# 80PIN_FMU_REV_1B.net
KiCad netlist of a schematic drawn in Altium Designer
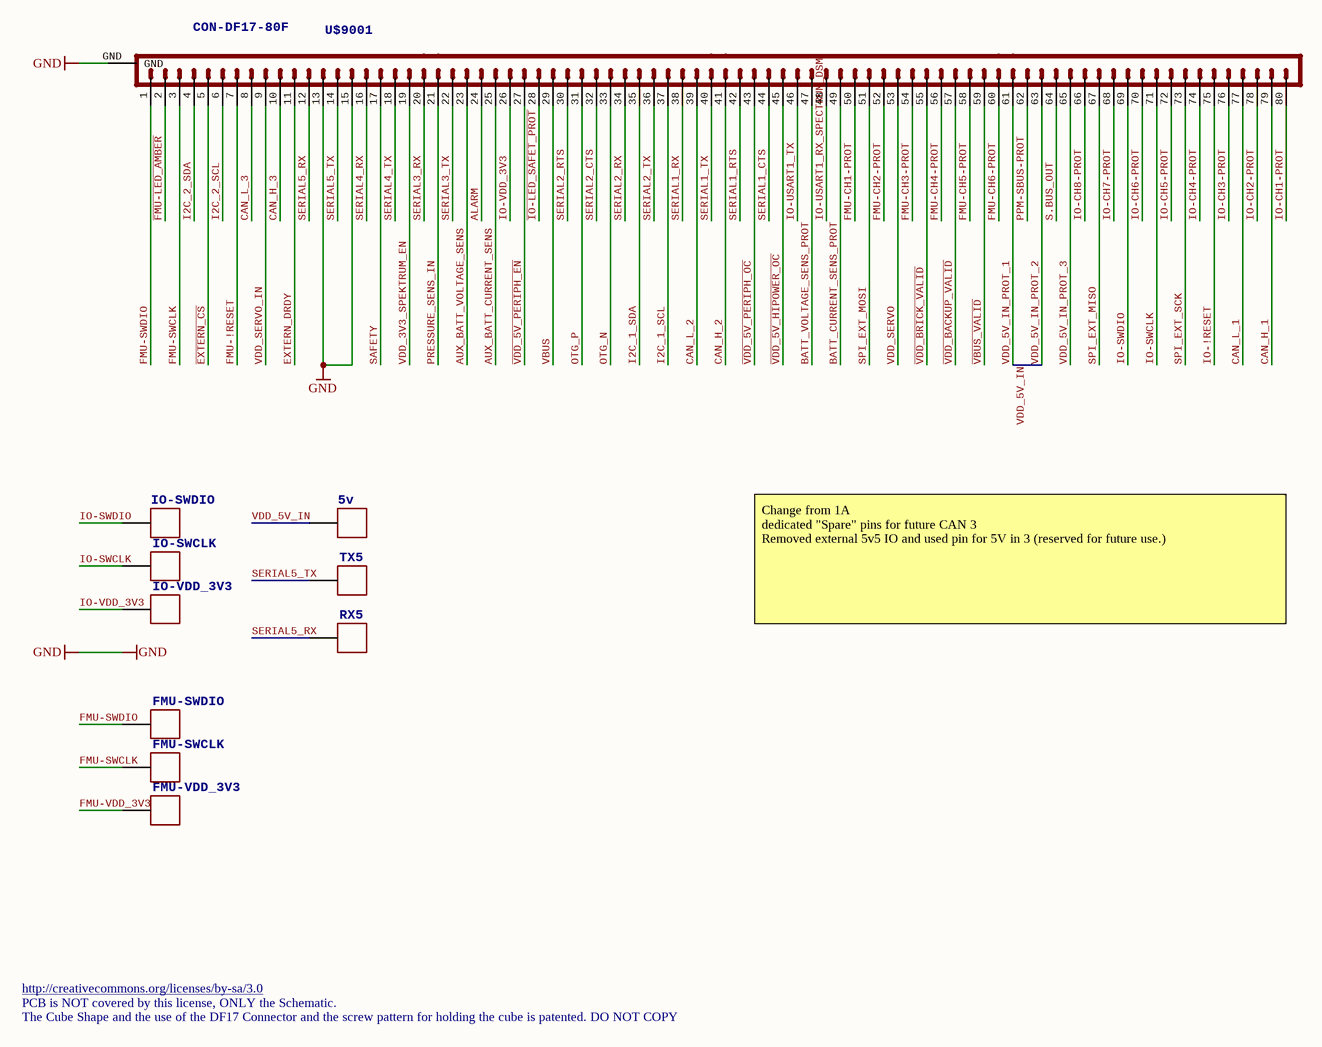
[diagram p0: 80PIN_FMU_REV_1B.SchDoc]

(export (version "E")
  (design (tool "Eeschema 10.0.6"))
  (components
    (comp (ref "5v") (value "PAD.04") (footprint "PAD.04X.04") (libsource (lib "pixhawk2") (part "PAD.04")))
    (comp (ref "FMU-SWCLK")
      (value "PAD.04")
      (footprint "PAD.04X.04")
      (libsource (lib "pixhawk2") (part "PAD.04"))
    )
    (comp (ref "FMU-SWDIO")
      (value "PAD.04")
      (footprint "PAD.04X.04")
      (libsource (lib "pixhawk2") (part "PAD.04"))
    )
    (comp (ref "FMU-VDD_3V3")
      (value "PAD.04")
      (footprint "PAD.04X.04")
      (libsource (lib "pixhawk2") (part "PAD.04"))
    )
    (comp (ref "IO-SWCLK")
      (value "PAD.04")
      (footprint "PAD.04X.04")
      (libsource (lib "pixhawk2") (part "PAD.04"))
    )
    (comp (ref "IO-SWDIO")
      (value "PAD.04")
      (footprint "PAD.04X.04")
      (libsource (lib "pixhawk2") (part "PAD.04"))
    )
    (comp (ref "IO-VDD_3V3")
      (value "PAD.04")
      (footprint "PAD.04X.04")
      (libsource (lib "pixhawk2") (part "PAD.04"))
    )
    (comp (ref "RX5") (value "PAD.04") (footprint "PAD.04X.04") (libsource (lib "pixhawk2") (part "PAD.04")))
    (comp (ref "TX5") (value "PAD.04") (footprint "PAD.04X.04") (libsource (lib "pixhawk2") (part "PAD.04")))
    (comp (ref "U$9001")
      (value "CON-DF17-80F")
      (footprint "CON-DF17-80F")
      (description "CONN RECEPT 80POS .5MM SMD W/FIT")
      (libsource (lib "pixhawk2") (part "CON-DF17-80F"))
    )
  )
  (nets
    (net (code "1") (name "/ALARM") (class "Default")
      (node (ref "U$9001") (pin "24") (pinfunction "24_24") (pintype "passive"))
    )
    (net (code "2") (name "/AUX_BATT_CURRENT_SENS") (class "Default")
      (node (ref "U$9001") (pin "25") (pinfunction "25_25") (pintype "passive"))
    )
    (net (code "3") (name "/AUX_BATT_VOLTAGE_SENS") (class "Default")
      (node (ref "U$9001") (pin "23") (pinfunction "23_23") (pintype "passive"))
    )
    (net (code "4") (name "/BATT_CURRENT_SENS_PROT") (class "Default")
      (node (ref "U$9001") (pin "49") (pinfunction "49_49") (pintype "passive"))
    )
    (net (code "5") (name "/BATT_VOLTAGE_SENS_PROT") (class "Default")
      (node (ref "U$9001") (pin "47") (pinfunction "47_47") (pintype "passive"))
    )
    (net (code "6") (name "/CAN_H_1") (class "Default")
      (node (ref "U$9001") (pin "79") (pinfunction "79_79") (pintype "passive"))
    )
    (net (code "7") (name "/CAN_H_2") (class "Default")
      (node (ref "U$9001") (pin "41") (pinfunction "41_41") (pintype "passive"))
    )
    (net (code "8") (name "/CAN_H_3") (class "Default")
      (node (ref "U$9001") (pin "10") (pinfunction "10_10") (pintype "passive"))
    )
    (net (code "9") (name "/CAN_L_1") (class "Default")
      (node (ref "U$9001") (pin "77") (pinfunction "77_77") (pintype "passive"))
    )
    (net (code "10") (name "/CAN_L_2") (class "Default")
      (node (ref "U$9001") (pin "39") (pinfunction "39_39") (pintype "passive"))
    )
    (net (code "11") (name "/CAN_L_3") (class "Default")
      (node (ref "U$9001") (pin "8") (pinfunction "8_8") (pintype "passive"))
    )
    (net (code "12") (name "/EXTERN_DRDY") (class "Default")
      (node (ref "U$9001") (pin "11") (pinfunction "11_11") (pintype "passive"))
    )
    (net (code "13") (name "/FMU-!RESET") (class "Default")
      (node (ref "U$9001") (pin "7") (pinfunction "7_7") (pintype "passive"))
    )
    (net (code "14") (name "/FMU-CH1-PROT") (class "Default")
      (node (ref "U$9001") (pin "50") (pinfunction "50_50") (pintype "passive"))
    )
    (net (code "15") (name "/FMU-CH2-PROT") (class "Default")
      (node (ref "U$9001") (pin "52") (pinfunction "52_52") (pintype "passive"))
    )
    (net (code "16") (name "/FMU-CH3-PROT") (class "Default")
      (node (ref "U$9001") (pin "54") (pinfunction "54_54") (pintype "passive"))
    )
    (net (code "17") (name "/FMU-CH4-PROT") (class "Default")
      (node (ref "U$9001") (pin "56") (pinfunction "56_56") (pintype "passive"))
    )
    (net (code "18") (name "/FMU-CH5-PROT") (class "Default")
      (node (ref "U$9001") (pin "58") (pinfunction "58_58") (pintype "passive"))
    )
    (net (code "19") (name "/FMU-CH6-PROT") (class "Default")
      (node (ref "U$9001") (pin "60") (pinfunction "60_60") (pintype "passive"))
    )
    (net (code "20") (name "/FMU-SWCLK") (class "Default")
      (node (ref "FMU-SWCLK") (pin "P$1") (pinfunction "P$1_P$1") (pintype "passive"))
      (node (ref "U$9001") (pin "3") (pinfunction "3_3") (pintype "passive"))
    )
    (net (code "21") (name "/FMU-SWDIO") (class "Default")
      (node (ref "FMU-SWDIO") (pin "P$1") (pinfunction "P$1_P$1") (pintype "passive"))
      (node (ref "U$9001") (pin "1") (pinfunction "1_1") (pintype "passive"))
    )
    (net (code "22") (name "/FMU-VDD_3V3") (class "Default")
      (node (ref "FMU-VDD_3V3") (pin "P$1") (pinfunction "P$1_P$1") (pintype "passive"))
    )
    (net (code "23") (name "/I2C_1_SCL") (class "Default")
      (node (ref "U$9001") (pin "37") (pinfunction "37_37") (pintype "passive"))
    )
    (net (code "24") (name "/I2C_1_SDA") (class "Default")
      (node (ref "U$9001") (pin "35") (pinfunction "35_35") (pintype "passive"))
    )
    (net (code "25") (name "/I2C_2_SCL") (class "Default")
      (node (ref "U$9001") (pin "6") (pinfunction "6_6") (pintype "passive"))
    )
    (net (code "26") (name "/I2C_2_SDA") (class "Default")
      (node (ref "U$9001") (pin "4") (pinfunction "4_4") (pintype "passive"))
    )
    (net (code "27") (name "/IO-!RESET") (class "Default")
      (node (ref "U$9001") (pin "75") (pinfunction "75_75") (pintype "passive"))
    )
    (net (code "28") (name "/IO-CH1-PROT") (class "Default")
      (node (ref "U$9001") (pin "80") (pinfunction "80_80") (pintype "passive"))
    )
    (net (code "29") (name "/IO-CH2-PROT") (class "Default")
      (node (ref "U$9001") (pin "78") (pinfunction "78_78") (pintype "passive"))
    )
    (net (code "30") (name "/IO-CH3-PROT") (class "Default")
      (node (ref "U$9001") (pin "76") (pinfunction "76_76") (pintype "passive"))
    )
    (net (code "31") (name "/IO-CH4-PROT") (class "Default")
      (node (ref "U$9001") (pin "74") (pinfunction "74_74") (pintype "passive"))
    )
    (net (code "32") (name "/IO-CH5-PROT") (class "Default")
      (node (ref "U$9001") (pin "72") (pinfunction "72_72") (pintype "passive"))
    )
    (net (code "33") (name "/IO-CH6-PROT") (class "Default")
      (node (ref "U$9001") (pin "70") (pinfunction "70_70") (pintype "passive"))
    )
    (net (code "34") (name "/IO-CH7-PROT") (class "Default")
      (node (ref "U$9001") (pin "68") (pinfunction "68_68") (pintype "passive"))
    )
    (net (code "35") (name "/IO-CH8-PROT") (class "Default")
      (node (ref "U$9001") (pin "66") (pinfunction "66_66") (pintype "passive"))
    )
    (net (code "36") (name "/IO-SWCLK") (class "Default")
      (node (ref "IO-SWCLK") (pin "P$1") (pinfunction "P$1_P$1") (pintype "passive"))
      (node (ref "U$9001") (pin "71") (pinfunction "71_71") (pintype "passive"))
    )
    (net (code "37") (name "/IO-SWDIO") (class "Default")
      (node (ref "IO-SWDIO") (pin "P$1") (pinfunction "P$1_P$1") (pintype "passive"))
      (node (ref "U$9001") (pin "69") (pinfunction "69_69") (pintype "passive"))
    )
    (net (code "38") (name "/IO-USART1_RX_SPECTRUM_DSM") (class "Default")
      (node (ref "U$9001") (pin "48") (pinfunction "48_48") (pintype "passive"))
    )
    (net (code "39") (name "/IO-USART1_TX") (class "Default")
      (node (ref "U$9001") (pin "46") (pinfunction "46_46") (pintype "passive"))
    )
    (net (code "40") (name "/IO-VDD_3V3") (class "Default")
      (node (ref "IO-VDD_3V3") (pin "P$1") (pinfunction "P$1_P$1") (pintype "passive"))
      (node (ref "U$9001") (pin "26") (pinfunction "26_26") (pintype "passive"))
    )
    (net (code "41") (name "/OTG_N") (class "Default")
      (node (ref "U$9001") (pin "33") (pinfunction "33_33") (pintype "passive"))
    )
    (net (code "42") (name "/OTG_P") (class "Default")
      (node (ref "U$9001") (pin "31") (pinfunction "31_31") (pintype "passive"))
    )
    (net (code "43") (name "/PPM-SBUS-PROT") (class "Default")
      (node (ref "U$9001") (pin "62") (pinfunction "62_62") (pintype "passive"))
    )
    (net (code "44") (name "/PRESSURE_SENS_IN") (class "Default")
      (node (ref "U$9001") (pin "21") (pinfunction "21_21") (pintype "passive"))
    )
    (net (code "45") (name "/S.BUS_OUT") (class "Default")
      (node (ref "U$9001") (pin "64") (pinfunction "64_64") (pintype "passive"))
    )
    (net (code "46") (name "/SAFETY") (class "Default")
      (node (ref "U$9001") (pin "17") (pinfunction "17_17") (pintype "passive"))
    )
    (net (code "47") (name "/SERIAL1_CTS") (class "Default")
      (node (ref "U$9001") (pin "44") (pinfunction "44_44") (pintype "passive"))
    )
    (net (code "48") (name "/SERIAL1_RTS") (class "Default")
      (node (ref "U$9001") (pin "42") (pinfunction "42_42") (pintype "passive"))
    )
    (net (code "49") (name "/SERIAL1_RX") (class "Default")
      (node (ref "U$9001") (pin "38") (pinfunction "38_38") (pintype "passive"))
    )
    (net (code "50") (name "/SERIAL1_TX") (class "Default")
      (node (ref "U$9001") (pin "40") (pinfunction "40_40") (pintype "passive"))
    )
    (net (code "51") (name "/SERIAL2_CTS") (class "Default")
      (node (ref "U$9001") (pin "32") (pinfunction "32_32") (pintype "passive"))
    )
    (net (code "52") (name "/SERIAL2_RTS") (class "Default")
      (node (ref "U$9001") (pin "30") (pinfunction "30_30") (pintype "passive"))
    )
    (net (code "53") (name "/SERIAL2_RX") (class "Default")
      (node (ref "U$9001") (pin "34") (pinfunction "34_34") (pintype "passive"))
    )
    (net (code "54") (name "/SERIAL2_TX") (class "Default")
      (node (ref "U$9001") (pin "36") (pinfunction "36_36") (pintype "passive"))
    )
    (net (code "55") (name "/SERIAL3_RX") (class "Default")
      (node (ref "U$9001") (pin "20") (pinfunction "20_20") (pintype "passive"))
    )
    (net (code "56") (name "/SERIAL3_TX") (class "Default")
      (node (ref "U$9001") (pin "22") (pinfunction "22_22") (pintype "passive"))
    )
    (net (code "57") (name "/SERIAL4_RX") (class "Default")
      (node (ref "U$9001") (pin "16") (pinfunction "16_16") (pintype "passive"))
    )
    (net (code "58") (name "/SERIAL4_TX") (class "Default")
      (node (ref "U$9001") (pin "18") (pinfunction "18_18") (pintype "passive"))
    )
    (net (code "59") (name "/SERIAL5_RX") (class "Default")
      (node (ref "RX5") (pin "P$1") (pinfunction "P$1_P$1") (pintype "passive"))
      (node (ref "U$9001") (pin "12") (pinfunction "12_12") (pintype "passive"))
    )
    (net (code "60") (name "/SERIAL5_TX") (class "Default")
      (node (ref "TX5") (pin "P$1") (pinfunction "P$1_P$1") (pintype "passive"))
      (node (ref "U$9001") (pin "14") (pinfunction "14_14") (pintype "passive"))
    )
    (net (code "61") (name "/SPI_EXT_MISO") (class "Default")
      (node (ref "U$9001") (pin "67") (pinfunction "67_67") (pintype "passive"))
    )
    (net (code "62") (name "/SPI_EXT_MOSI") (class "Default")
      (node (ref "U$9001") (pin "51") (pinfunction "51_51") (pintype "passive"))
    )
    (net (code "63") (name "/SPI_EXT_SCK") (class "Default")
      (node (ref "U$9001") (pin "73") (pinfunction "73_73") (pintype "passive"))
    )
    (net (code "64") (name "/VBUS") (class "Default")
      (node (ref "U$9001") (pin "29") (pinfunction "29_29") (pintype "passive"))
    )
    (net (code "65") (name "/VDD_3V3_SPEKTRUM_EN") (class "Default")
      (node (ref "U$9001") (pin "19") (pinfunction "19_19") (pintype "passive"))
    )
    (net (code "66") (name "/VDD_5V_IN") (class "Default")
      (node (ref "5v") (pin "P$1") (pinfunction "P$1_P$1") (pintype "passive"))
      (node (ref "U$9001") (pin "61") (pinfunction "61_61") (pintype "passive"))
      (node (ref "U$9001") (pin "63") (pinfunction "63_63") (pintype "passive"))
    )
    (net (code "67") (name "/VDD_5V_IN_PROT_3") (class "Default")
      (node (ref "U$9001") (pin "65") (pinfunction "65_65") (pintype "passive"))
    )
    (net (code "68") (name "/VDD_SERVO") (class "Default")
      (node (ref "U$9001") (pin "53") (pinfunction "53_53") (pintype "passive"))
    )
    (net (code "69") (name "/VDD_SERVO_IN") (class "Default")
      (node (ref "U$9001") (pin "9") (pinfunction "9_9") (pintype "passive"))
    )
    (net (code "70") (name "/~{EXTERN_CS}") (class "Default")
      (node (ref "U$9001") (pin "5") (pinfunction "5_5") (pintype "passive"))
    )
    (net (code "71") (name "/~{FMU-LED_AMBER}") (class "Default")
      (node (ref "U$9001") (pin "2") (pinfunction "2_2") (pintype "passive"))
    )
    (net (code "72") (name "/~{IO-LED_SAFET_PROT}") (class "Default")
      (node (ref "U$9001") (pin "28") (pinfunction "28_28") (pintype "passive"))
    )
    (net (code "73") (name "/~{VBUS_VALID}") (class "Default")
      (node (ref "U$9001") (pin "59") (pinfunction "59_59") (pintype "passive"))
    )
    (net (code "74") (name "/~{VDD_5V_HIPOWER_OC}") (class "Default")
      (node (ref "U$9001") (pin "45") (pinfunction "45_45") (pintype "passive"))
    )
    (net (code "75") (name "/~{VDD_5V_PERIPH_EN}") (class "Default")
      (node (ref "U$9001") (pin "27") (pinfunction "27_27") (pintype "passive"))
    )
    (net (code "76") (name "/~{VDD_5V_PERIPH_OC}") (class "Default")
      (node (ref "U$9001") (pin "43") (pinfunction "43_43") (pintype "passive"))
    )
    (net (code "77") (name "/~{VDD_BACKUP_VALID}") (class "Default")
      (node (ref "U$9001") (pin "57") (pinfunction "57_57") (pintype "passive"))
    )
    (net (code "78") (name "/~{VDD_BRICK_VALID}") (class "Default")
      (node (ref "U$9001") (pin "55") (pinfunction "55_55") (pintype "passive"))
    )
    (net (code "79") (name "GND") (class "Default")
      (node (ref "U$9001") (pin "13") (pinfunction "13_13") (pintype "passive"))
      (node (ref "U$9001") (pin "15") (pinfunction "15_15") (pintype "passive"))
      (node (ref "U$9001") (pin "GND") (pinfunction "GND_GND") (pintype "passive"))
    )
  )
)
